# BTB_Connector_H.net
KiCad netlist of a schematic drawn in Altium Designer
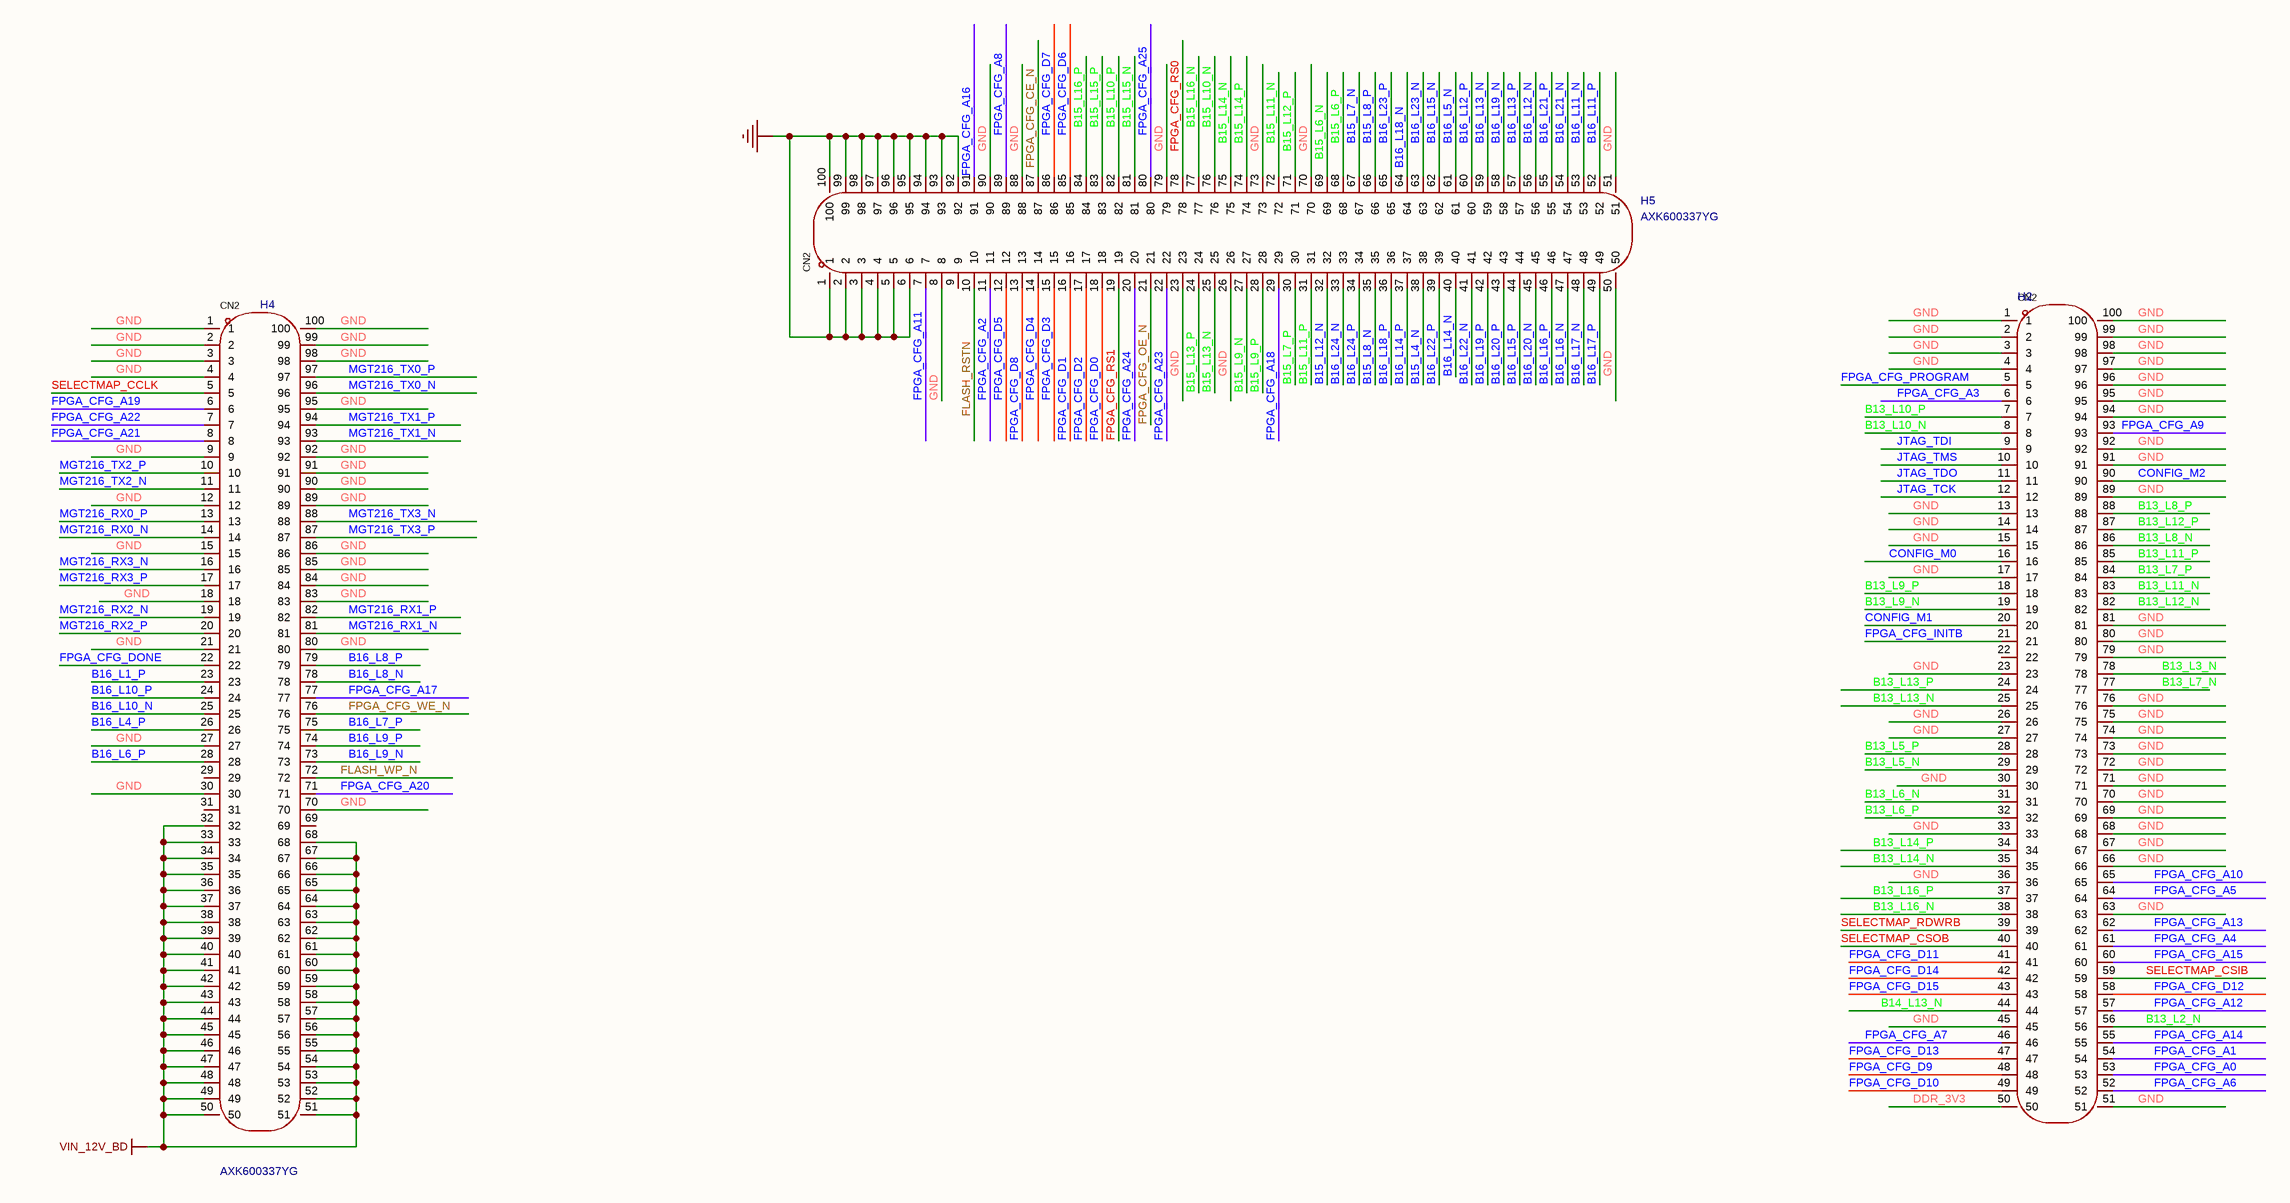
[diagram p0: BTB_Connector_H.schdoc]

(export (version "E")
  (design (tool "Eeschema 10.0.6"))
  (components
    (comp (ref "H2")
      (value "~")
      (footprint "AXK600337YG")
      (libsource (lib "altium-import") (part "root_0_AXK600337YG_"))
    )
    (comp (ref "H4")
      (value "~")
      (footprint "AXK600337YG")
      (fields (field (name "DEVICE") "AXK600337YG"))
      (libsource (lib "altium-import") (part "root_0_AXK600337YG_"))
    )
    (comp (ref "H5")
      (value "~")
      (footprint "AXK600337YG")
      (fields (field (name "DEVICE") "AXK600337YG"))
      (libsource (lib "altium-import") (part "root_1_AXK600337YG_"))
    )
  )
  (nets
    (net (code "1") (name "/B13_L2_N") (class "Default")
      (node (ref "H2") (pin "56") (pinfunction "56_56") (pintype "passive"))
    )
    (net (code "2") (name "/B13_L3_N") (class "Default")
      (node (ref "H2") (pin "78") (pinfunction "78_78") (pintype "passive"))
    )
    (net (code "3") (name "/B13_L5_N") (class "Default")
      (node (ref "H2") (pin "29") (pinfunction "29_29") (pintype "passive"))
    )
    (net (code "4") (name "/B13_L5_P") (class "Default")
      (node (ref "H2") (pin "28") (pinfunction "28_28") (pintype "passive"))
    )
    (net (code "5") (name "/B13_L6_N") (class "Default")
      (node (ref "H2") (pin "31") (pinfunction "31_31") (pintype "passive"))
    )
    (net (code "6") (name "/B13_L6_P") (class "Default")
      (node (ref "H2") (pin "32") (pinfunction "32_32") (pintype "passive"))
    )
    (net (code "7") (name "/B13_L7_N") (class "Default")
      (node (ref "H2") (pin "77") (pinfunction "77_77") (pintype "passive"))
    )
    (net (code "8") (name "/B13_L7_P") (class "Default")
      (node (ref "H2") (pin "84") (pinfunction "84_84") (pintype "passive"))
    )
    (net (code "9") (name "/B13_L8_N") (class "Default")
      (node (ref "H2") (pin "86") (pinfunction "86_86") (pintype "passive"))
    )
    (net (code "10") (name "/B13_L8_P") (class "Default")
      (node (ref "H2") (pin "88") (pinfunction "88_88") (pintype "passive"))
    )
    (net (code "11") (name "/B13_L9_N") (class "Default")
      (node (ref "H2") (pin "19") (pinfunction "19_19") (pintype "passive"))
    )
    (net (code "12") (name "/B13_L9_P") (class "Default")
      (node (ref "H2") (pin "18") (pinfunction "18_18") (pintype "passive"))
    )
    (net (code "13") (name "/B13_L10_N") (class "Default")
      (node (ref "H2") (pin "8") (pinfunction "8_8") (pintype "passive"))
    )
    (net (code "14") (name "/B13_L10_P") (class "Default")
      (node (ref "H2") (pin "7") (pinfunction "7_7") (pintype "passive"))
    )
    (net (code "15") (name "/B13_L11_N") (class "Default")
      (node (ref "H2") (pin "83") (pinfunction "83_83") (pintype "passive"))
    )
    (net (code "16") (name "/B13_L11_P") (class "Default")
      (node (ref "H2") (pin "85") (pinfunction "85_85") (pintype "passive"))
    )
    (net (code "17") (name "/B13_L12_N") (class "Default")
      (node (ref "H2") (pin "82") (pinfunction "82_82") (pintype "passive"))
    )
    (net (code "18") (name "/B13_L12_P") (class "Default")
      (node (ref "H2") (pin "87") (pinfunction "87_87") (pintype "passive"))
    )
    (net (code "19") (name "/B13_L13_N") (class "Default")
      (node (ref "H2") (pin "25") (pinfunction "25_25") (pintype "passive"))
    )
    (net (code "20") (name "/B13_L13_P") (class "Default")
      (node (ref "H2") (pin "24") (pinfunction "24_24") (pintype "passive"))
    )
    (net (code "21") (name "/B13_L14_N") (class "Default")
      (node (ref "H2") (pin "35") (pinfunction "35_35") (pintype "passive"))
    )
    (net (code "22") (name "/B13_L14_P") (class "Default")
      (node (ref "H2") (pin "34") (pinfunction "34_34") (pintype "passive"))
    )
    (net (code "23") (name "/B13_L16_N") (class "Default")
      (node (ref "H2") (pin "38") (pinfunction "38_38") (pintype "passive"))
    )
    (net (code "24") (name "/B13_L16_P") (class "Default")
      (node (ref "H2") (pin "37") (pinfunction "37_37") (pintype "passive"))
    )
    (net (code "25") (name "/B14_L13_N") (class "Default")
      (node (ref "H2") (pin "44") (pinfunction "44_44") (pintype "passive"))
    )
    (net (code "26") (name "/B15_L4_N") (class "Default")
      (node (ref "H5") (pin "38") (pinfunction "38_38") (pintype "passive"))
    )
    (net (code "27") (name "/B15_L6_N") (class "Default")
      (node (ref "H5") (pin "69") (pinfunction "69_69") (pintype "passive"))
    )
    (net (code "28") (name "/B15_L6_P") (class "Default")
      (node (ref "H5") (pin "68") (pinfunction "68_68") (pintype "passive"))
    )
    (net (code "29") (name "/B15_L7_N") (class "Default")
      (node (ref "H5") (pin "67") (pinfunction "67_67") (pintype "passive"))
    )
    (net (code "30") (name "/B15_L7_P") (class "Default")
      (node (ref "H5") (pin "30") (pinfunction "30_30") (pintype "passive"))
    )
    (net (code "31") (name "/B15_L8_N") (class "Default")
      (node (ref "H5") (pin "35") (pinfunction "35_35") (pintype "passive"))
    )
    (net (code "32") (name "/B15_L8_P") (class "Default")
      (node (ref "H5") (pin "66") (pinfunction "66_66") (pintype "passive"))
    )
    (net (code "33") (name "/B15_L9_N") (class "Default")
      (node (ref "H5") (pin "27") (pinfunction "27_27") (pintype "passive"))
    )
    (net (code "34") (name "/B15_L9_P") (class "Default")
      (node (ref "H5") (pin "28") (pinfunction "28_28") (pintype "passive"))
    )
    (net (code "35") (name "/B15_L10_N") (class "Default")
      (node (ref "H5") (pin "76") (pinfunction "76_76") (pintype "passive"))
    )
    (net (code "36") (name "/B15_L10_P") (class "Default")
      (node (ref "H5") (pin "82") (pinfunction "82_82") (pintype "passive"))
    )
    (net (code "37") (name "/B15_L11_N") (class "Default")
      (node (ref "H5") (pin "72") (pinfunction "72_72") (pintype "passive"))
    )
    (net (code "38") (name "/B15_L11_P") (class "Default")
      (node (ref "H5") (pin "31") (pinfunction "31_31") (pintype "passive"))
    )
    (net (code "39") (name "/B15_L12_N") (class "Default")
      (node (ref "H5") (pin "32") (pinfunction "32_32") (pintype "passive"))
    )
    (net (code "40") (name "/B15_L12_P") (class "Default")
      (node (ref "H5") (pin "71") (pinfunction "71_71") (pintype "passive"))
    )
    (net (code "41") (name "/B15_L13_N") (class "Default")
      (node (ref "H5") (pin "25") (pinfunction "25_25") (pintype "passive"))
    )
    (net (code "42") (name "/B15_L13_P") (class "Default")
      (node (ref "H5") (pin "24") (pinfunction "24_24") (pintype "passive"))
    )
    (net (code "43") (name "/B15_L14_N") (class "Default")
      (node (ref "H5") (pin "75") (pinfunction "75_75") (pintype "passive"))
    )
    (net (code "44") (name "/B15_L14_P") (class "Default")
      (node (ref "H5") (pin "74") (pinfunction "74_74") (pintype "passive"))
    )
    (net (code "45") (name "/B15_L15_N") (class "Default")
      (node (ref "H5") (pin "81") (pinfunction "81_81") (pintype "passive"))
    )
    (net (code "46") (name "/B15_L15_P") (class "Default")
      (node (ref "H5") (pin "83") (pinfunction "83_83") (pintype "passive"))
    )
    (net (code "47") (name "/B15_L16_N") (class "Default")
      (node (ref "H5") (pin "77") (pinfunction "77_77") (pintype "passive"))
    )
    (net (code "48") (name "/B15_L16_P") (class "Default")
      (node (ref "H5") (pin "84") (pinfunction "84_84") (pintype "passive"))
    )
    (net (code "49") (name "/B16_L1_P") (class "Default")
      (node (ref "H4") (pin "23") (pinfunction "23_23") (pintype "passive"))
    )
    (net (code "50") (name "/B16_L4_P") (class "Default")
      (node (ref "H4") (pin "26") (pinfunction "26_26") (pintype "passive"))
    )
    (net (code "51") (name "/B16_L5_N") (class "Default")
      (node (ref "H5") (pin "61") (pinfunction "61_61") (pintype "passive"))
    )
    (net (code "52") (name "/B16_L6_P") (class "Default")
      (node (ref "H4") (pin "28") (pinfunction "28_28") (pintype "passive"))
    )
    (net (code "53") (name "/B16_L7_P") (class "Default")
      (node (ref "H4") (pin "75") (pinfunction "75_75") (pintype "passive"))
    )
    (net (code "54") (name "/B16_L8_N") (class "Default")
      (node (ref "H4") (pin "78") (pinfunction "78_78") (pintype "passive"))
    )
    (net (code "55") (name "/B16_L8_P") (class "Default")
      (node (ref "H4") (pin "79") (pinfunction "79_79") (pintype "passive"))
    )
    (net (code "56") (name "/B16_L9_N") (class "Default")
      (node (ref "H4") (pin "73") (pinfunction "73_73") (pintype "passive"))
    )
    (net (code "57") (name "/B16_L9_P") (class "Default")
      (node (ref "H4") (pin "74") (pinfunction "74_74") (pintype "passive"))
    )
    (net (code "58") (name "/B16_L10_N") (class "Default")
      (node (ref "H4") (pin "25") (pinfunction "25_25") (pintype "passive"))
    )
    (net (code "59") (name "/B16_L10_P") (class "Default")
      (node (ref "H4") (pin "24") (pinfunction "24_24") (pintype "passive"))
    )
    (net (code "60") (name "/B16_L11_N") (class "Default")
      (node (ref "H5") (pin "53") (pinfunction "53_53") (pintype "passive"))
    )
    (net (code "61") (name "/B16_L11_P") (class "Default")
      (node (ref "H5") (pin "52") (pinfunction "52_52") (pintype "passive"))
    )
    (net (code "62") (name "/B16_L12_N") (class "Default")
      (node (ref "H5") (pin "56") (pinfunction "56_56") (pintype "passive"))
    )
    (net (code "63") (name "/B16_L12_P") (class "Default")
      (node (ref "H5") (pin "60") (pinfunction "60_60") (pintype "passive"))
    )
    (net (code "64") (name "/B16_L13_N") (class "Default")
      (node (ref "H5") (pin "59") (pinfunction "59_59") (pintype "passive"))
    )
    (net (code "65") (name "/B16_L13_P") (class "Default")
      (node (ref "H5") (pin "57") (pinfunction "57_57") (pintype "passive"))
    )
    (net (code "66") (name "/B16_L14_N") (class "Default")
      (node (ref "H5") (pin "40") (pinfunction "40_40") (pintype "passive"))
    )
    (net (code "67") (name "/B16_L14_P") (class "Default")
      (node (ref "H5") (pin "37") (pinfunction "37_37") (pintype "passive"))
    )
    (net (code "68") (name "/B16_L15_N") (class "Default")
      (node (ref "H5") (pin "62") (pinfunction "62_62") (pintype "passive"))
    )
    (net (code "69") (name "/B16_L15_P") (class "Default")
      (node (ref "H5") (pin "44") (pinfunction "44_44") (pintype "passive"))
    )
    (net (code "70") (name "/B16_L16_N") (class "Default")
      (node (ref "H5") (pin "47") (pinfunction "47_47") (pintype "passive"))
    )
    (net (code "71") (name "/B16_L16_P") (class "Default")
      (node (ref "H5") (pin "46") (pinfunction "46_46") (pintype "passive"))
    )
    (net (code "72") (name "/B16_L17_N") (class "Default")
      (node (ref "H5") (pin "48") (pinfunction "48_48") (pintype "passive"))
    )
    (net (code "73") (name "/B16_L17_P") (class "Default")
      (node (ref "H5") (pin "49") (pinfunction "49_49") (pintype "passive"))
    )
    (net (code "74") (name "/B16_L18_N") (class "Default")
      (node (ref "H5") (pin "64") (pinfunction "64_64") (pintype "passive"))
    )
    (net (code "75") (name "/B16_L18_P") (class "Default")
      (node (ref "H5") (pin "36") (pinfunction "36_36") (pintype "passive"))
    )
    (net (code "76") (name "/B16_L19_N") (class "Default")
      (node (ref "H5") (pin "58") (pinfunction "58_58") (pintype "passive"))
    )
    (net (code "77") (name "/B16_L19_P") (class "Default")
      (node (ref "H5") (pin "42") (pinfunction "42_42") (pintype "passive"))
    )
    (net (code "78") (name "/B16_L20_N") (class "Default")
      (node (ref "H5") (pin "45") (pinfunction "45_45") (pintype "passive"))
    )
    (net (code "79") (name "/B16_L20_P") (class "Default")
      (node (ref "H5") (pin "43") (pinfunction "43_43") (pintype "passive"))
    )
    (net (code "80") (name "/B16_L21_N") (class "Default")
      (node (ref "H5") (pin "54") (pinfunction "54_54") (pintype "passive"))
    )
    (net (code "81") (name "/B16_L21_P") (class "Default")
      (node (ref "H5") (pin "55") (pinfunction "55_55") (pintype "passive"))
    )
    (net (code "82") (name "/B16_L22_N") (class "Default")
      (node (ref "H5") (pin "41") (pinfunction "41_41") (pintype "passive"))
    )
    (net (code "83") (name "/B16_L22_P") (class "Default")
      (node (ref "H5") (pin "39") (pinfunction "39_39") (pintype "passive"))
    )
    (net (code "84") (name "/B16_L23_N") (class "Default")
      (node (ref "H5") (pin "63") (pinfunction "63_63") (pintype "passive"))
    )
    (net (code "85") (name "/B16_L23_P") (class "Default")
      (node (ref "H5") (pin "65") (pinfunction "65_65") (pintype "passive"))
    )
    (net (code "86") (name "/B16_L24_N") (class "Default")
      (node (ref "H5") (pin "33") (pinfunction "33_33") (pintype "passive"))
    )
    (net (code "87") (name "/B16_L24_P") (class "Default")
      (node (ref "H5") (pin "34") (pinfunction "34_34") (pintype "passive"))
    )
    (net (code "88") (name "/CONFIG_M0") (class "Default")
      (node (ref "H2") (pin "16") (pinfunction "16_16") (pintype "passive"))
    )
    (net (code "89") (name "/CONFIG_M1") (class "Default")
      (node (ref "H2") (pin "20") (pinfunction "20_20") (pintype "passive"))
    )
    (net (code "90") (name "/CONFIG_M2") (class "Default")
      (node (ref "H2") (pin "90") (pinfunction "90_90") (pintype "passive"))
    )
    (net (code "91") (name "/DDR_3V3") (class "Default")
      (node (ref "H2") (pin "50") (pinfunction "50_50") (pintype "passive"))
    )
    (net (code "92") (name "/FLASH_RSTN") (class "Default")
      (node (ref "H5") (pin "10") (pinfunction "10_10") (pintype "passive"))
    )
    (net (code "93") (name "/FLASH_WP_N") (class "Default")
      (node (ref "H4") (pin "72") (pinfunction "72_72") (pintype "passive"))
    )
    (net (code "94") (name "/FPGA_CFG_A0") (class "Default")
      (node (ref "H2") (pin "53") (pinfunction "53_53") (pintype "passive"))
    )
    (net (code "95") (name "/FPGA_CFG_A1") (class "Default")
      (node (ref "H2") (pin "54") (pinfunction "54_54") (pintype "passive"))
    )
    (net (code "96") (name "/FPGA_CFG_A2") (class "Default")
      (node (ref "H5") (pin "11") (pinfunction "11_11") (pintype "passive"))
    )
    (net (code "97") (name "/FPGA_CFG_A3") (class "Default")
      (node (ref "H2") (pin "6") (pinfunction "6_6") (pintype "passive"))
    )
    (net (code "98") (name "/FPGA_CFG_A4") (class "Default")
      (node (ref "H2") (pin "61") (pinfunction "61_61") (pintype "passive"))
    )
    (net (code "99") (name "/FPGA_CFG_A5") (class "Default")
      (node (ref "H2") (pin "64") (pinfunction "64_64") (pintype "passive"))
    )
    (net (code "100") (name "/FPGA_CFG_A6") (class "Default")
      (node (ref "H2") (pin "52") (pinfunction "52_52") (pintype "passive"))
    )
    (net (code "101") (name "/FPGA_CFG_A7") (class "Default")
      (node (ref "H2") (pin "46") (pinfunction "46_46") (pintype "passive"))
    )
    (net (code "102") (name "/FPGA_CFG_A8") (class "Default")
      (node (ref "H5") (pin "89") (pinfunction "89_89") (pintype "passive"))
    )
    (net (code "103") (name "/FPGA_CFG_A9") (class "Default")
      (node (ref "H2") (pin "93") (pinfunction "93_93") (pintype "passive"))
    )
    (net (code "104") (name "/FPGA_CFG_A10") (class "Default")
      (node (ref "H2") (pin "65") (pinfunction "65_65") (pintype "passive"))
    )
    (net (code "105") (name "/FPGA_CFG_A11") (class "Default")
      (node (ref "H5") (pin "7") (pinfunction "7_7") (pintype "passive"))
    )
    (net (code "106") (name "/FPGA_CFG_A12") (class "Default")
      (node (ref "H2") (pin "57") (pinfunction "57_57") (pintype "passive"))
    )
    (net (code "107") (name "/FPGA_CFG_A13") (class "Default")
      (node (ref "H2") (pin "62") (pinfunction "62_62") (pintype "passive"))
    )
    (net (code "108") (name "/FPGA_CFG_A14") (class "Default")
      (node (ref "H2") (pin "55") (pinfunction "55_55") (pintype "passive"))
    )
    (net (code "109") (name "/FPGA_CFG_A15") (class "Default")
      (node (ref "H2") (pin "60") (pinfunction "60_60") (pintype "passive"))
    )
    (net (code "110") (name "/FPGA_CFG_A16") (class "Default")
      (node (ref "H5") (pin "91") (pinfunction "91_91") (pintype "passive"))
    )
    (net (code "111") (name "/FPGA_CFG_A17") (class "Default")
      (node (ref "H4") (pin "77") (pinfunction "77_77") (pintype "passive"))
    )
    (net (code "112") (name "/FPGA_CFG_A18") (class "Default")
      (node (ref "H5") (pin "29") (pinfunction "29_29") (pintype "passive"))
    )
    (net (code "113") (name "/FPGA_CFG_A19") (class "Default")
      (node (ref "H4") (pin "6") (pinfunction "6_6") (pintype "passive"))
    )
    (net (code "114") (name "/FPGA_CFG_A20") (class "Default")
      (node (ref "H4") (pin "71") (pinfunction "71_71") (pintype "passive"))
    )
    (net (code "115") (name "/FPGA_CFG_A21") (class "Default")
      (node (ref "H4") (pin "8") (pinfunction "8_8") (pintype "passive"))
    )
    (net (code "116") (name "/FPGA_CFG_A22") (class "Default")
      (node (ref "H4") (pin "7") (pinfunction "7_7") (pintype "passive"))
    )
    (net (code "117") (name "/FPGA_CFG_A23") (class "Default")
      (node (ref "H5") (pin "22") (pinfunction "22_22") (pintype "passive"))
    )
    (net (code "118") (name "/FPGA_CFG_A24") (class "Default")
      (node (ref "H5") (pin "20") (pinfunction "20_20") (pintype "passive"))
    )
    (net (code "119") (name "/FPGA_CFG_A25") (class "Default")
      (node (ref "H5") (pin "80") (pinfunction "80_80") (pintype "passive"))
    )
    (net (code "120") (name "/FPGA_CFG_CE_N") (class "Default")
      (node (ref "H5") (pin "87") (pinfunction "87_87") (pintype "passive"))
    )
    (net (code "121") (name "/FPGA_CFG_D0") (class "Default")
      (node (ref "H5") (pin "18") (pinfunction "18_18") (pintype "passive"))
    )
    (net (code "122") (name "/FPGA_CFG_D1") (class "Default")
      (node (ref "H5") (pin "16") (pinfunction "16_16") (pintype "passive"))
    )
    (net (code "123") (name "/FPGA_CFG_D2") (class "Default")
      (node (ref "H5") (pin "17") (pinfunction "17_17") (pintype "passive"))
    )
    (net (code "124") (name "/FPGA_CFG_D3") (class "Default")
      (node (ref "H5") (pin "15") (pinfunction "15_15") (pintype "passive"))
    )
    (net (code "125") (name "/FPGA_CFG_D4") (class "Default")
      (node (ref "H5") (pin "14") (pinfunction "14_14") (pintype "passive"))
    )
    (net (code "126") (name "/FPGA_CFG_D5") (class "Default")
      (node (ref "H5") (pin "12") (pinfunction "12_12") (pintype "passive"))
    )
    (net (code "127") (name "/FPGA_CFG_D6") (class "Default")
      (node (ref "H5") (pin "85") (pinfunction "85_85") (pintype "passive"))
    )
    (net (code "128") (name "/FPGA_CFG_D7") (class "Default")
      (node (ref "H5") (pin "86") (pinfunction "86_86") (pintype "passive"))
    )
    (net (code "129") (name "/FPGA_CFG_D8") (class "Default")
      (node (ref "H5") (pin "13") (pinfunction "13_13") (pintype "passive"))
    )
    (net (code "130") (name "/FPGA_CFG_D9") (class "Default")
      (node (ref "H2") (pin "48") (pinfunction "48_48") (pintype "passive"))
    )
    (net (code "131") (name "/FPGA_CFG_D10") (class "Default")
      (node (ref "H2") (pin "49") (pinfunction "49_49") (pintype "passive"))
    )
    (net (code "132") (name "/FPGA_CFG_D11") (class "Default")
      (node (ref "H2") (pin "41") (pinfunction "41_41") (pintype "passive"))
    )
    (net (code "133") (name "/FPGA_CFG_D12") (class "Default")
      (node (ref "H2") (pin "58") (pinfunction "58_58") (pintype "passive"))
    )
    (net (code "134") (name "/FPGA_CFG_D13") (class "Default")
      (node (ref "H2") (pin "47") (pinfunction "47_47") (pintype "passive"))
    )
    (net (code "135") (name "/FPGA_CFG_D14") (class "Default")
      (node (ref "H2") (pin "42") (pinfunction "42_42") (pintype "passive"))
    )
    (net (code "136") (name "/FPGA_CFG_D15") (class "Default")
      (node (ref "H2") (pin "43") (pinfunction "43_43") (pintype "passive"))
    )
    (net (code "137") (name "/FPGA_CFG_DONE") (class "Default")
      (node (ref "H4") (pin "22") (pinfunction "22_22") (pintype "passive"))
    )
    (net (code "138") (name "/FPGA_CFG_INITB") (class "Default")
      (node (ref "H2") (pin "21") (pinfunction "21_21") (pintype "passive"))
    )
    (net (code "139") (name "/FPGA_CFG_OE_N") (class "Default")
      (node (ref "H5") (pin "21") (pinfunction "21_21") (pintype "passive"))
    )
    (net (code "140") (name "/FPGA_CFG_PROGRAM") (class "Default")
      (node (ref "H2") (pin "5") (pinfunction "5_5") (pintype "passive"))
    )
    (net (code "141") (name "/FPGA_CFG_RS0") (class "Default")
      (node (ref "H5") (pin "78") (pinfunction "78_78") (pintype "passive"))
    )
    (net (code "142") (name "/FPGA_CFG_RS1") (class "Default")
      (node (ref "H5") (pin "19") (pinfunction "19_19") (pintype "passive"))
    )
    (net (code "143") (name "/FPGA_CFG_WE_N") (class "Default")
      (node (ref "H4") (pin "76") (pinfunction "76_76") (pintype "passive"))
    )
    (net (code "144") (name "/JTAG_TCK") (class "Default")
      (node (ref "H2") (pin "12") (pinfunction "12_12") (pintype "passive"))
    )
    (net (code "145") (name "/JTAG_TDI") (class "Default")
      (node (ref "H2") (pin "9") (pinfunction "9_9") (pintype "passive"))
    )
    (net (code "146") (name "/JTAG_TDO") (class "Default")
      (node (ref "H2") (pin "11") (pinfunction "11_11") (pintype "passive"))
    )
    (net (code "147") (name "/JTAG_TMS") (class "Default")
      (node (ref "H2") (pin "10") (pinfunction "10_10") (pintype "passive"))
    )
    (net (code "148") (name "/MGT216_RX0_N") (class "Default")
      (node (ref "H4") (pin "14") (pinfunction "14_14") (pintype "passive"))
    )
    (net (code "149") (name "/MGT216_RX0_P") (class "Default")
      (node (ref "H4") (pin "13") (pinfunction "13_13") (pintype "passive"))
    )
    (net (code "150") (name "/MGT216_RX1_N") (class "Default")
      (node (ref "H4") (pin "81") (pinfunction "81_81") (pintype "passive"))
    )
    (net (code "151") (name "/MGT216_RX1_P") (class "Default")
      (node (ref "H4") (pin "82") (pinfunction "82_82") (pintype "passive"))
    )
    (net (code "152") (name "/MGT216_RX2_N") (class "Default")
      (node (ref "H4") (pin "19") (pinfunction "19_19") (pintype "passive"))
    )
    (net (code "153") (name "/MGT216_RX2_P") (class "Default")
      (node (ref "H4") (pin "20") (pinfunction "20_20") (pintype "passive"))
    )
    (net (code "154") (name "/MGT216_RX3_N") (class "Default")
      (node (ref "H4") (pin "16") (pinfunction "16_16") (pintype "passive"))
    )
    (net (code "155") (name "/MGT216_RX3_P") (class "Default")
      (node (ref "H4") (pin "17") (pinfunction "17_17") (pintype "passive"))
    )
    (net (code "156") (name "/MGT216_TX0_N") (class "Default")
      (node (ref "H4") (pin "96") (pinfunction "96_96") (pintype "passive"))
    )
    (net (code "157") (name "/MGT216_TX0_P") (class "Default")
      (node (ref "H4") (pin "97") (pinfunction "97_97") (pintype "passive"))
    )
    (net (code "158") (name "/MGT216_TX1_N") (class "Default")
      (node (ref "H4") (pin "93") (pinfunction "93_93") (pintype "passive"))
    )
    (net (code "159") (name "/MGT216_TX1_P") (class "Default")
      (node (ref "H4") (pin "94") (pinfunction "94_94") (pintype "passive"))
    )
    (net (code "160") (name "/MGT216_TX2_N") (class "Default")
      (node (ref "H4") (pin "11") (pinfunction "11_11") (pintype "passive"))
    )
    (net (code "161") (name "/MGT216_TX2_P") (class "Default")
      (node (ref "H4") (pin "10") (pinfunction "10_10") (pintype "passive"))
    )
    (net (code "162") (name "/MGT216_TX3_N") (class "Default")
      (node (ref "H4") (pin "88") (pinfunction "88_88") (pintype "passive"))
    )
    (net (code "163") (name "/MGT216_TX3_P") (class "Default")
      (node (ref "H4") (pin "87") (pinfunction "87_87") (pintype "passive"))
    )
    (net (code "164") (name "/SELECTMAP_CCLK") (class "Default")
      (node (ref "H4") (pin "5") (pinfunction "5_5") (pintype "passive"))
    )
    (net (code "165") (name "/SELECTMAP_CSIB") (class "Default")
      (node (ref "H2") (pin "59") (pinfunction "59_59") (pintype "passive"))
    )
    (net (code "166") (name "/SELECTMAP_CSOB") (class "Default")
      (node (ref "H2") (pin "40") (pinfunction "40_40") (pintype "passive"))
    )
    (net (code "167") (name "/SELECTMAP_RDWRB") (class "Default")
      (node (ref "H2") (pin "39") (pinfunction "39_39") (pintype "passive"))
    )
    (net (code "168") (name "GND") (class "Default")
      (node (ref "H2") (pin "1") (pinfunction "1_1") (pintype "passive"))
      (node (ref "H2") (pin "100") (pinfunction "100_100") (pintype "passive"))
      (node (ref "H2") (pin "13") (pinfunction "13_13") (pintype "passive"))
      (node (ref "H2") (pin "14") (pinfunction "14_14") (pintype "passive"))
      (node (ref "H2") (pin "15") (pinfunction "15_15") (pintype "passive"))
      (node (ref "H2") (pin "17") (pinfunction "17_17") (pintype "passive"))
      (node (ref "H2") (pin "2") (pinfunction "2_2") (pintype "passive"))
      (node (ref "H2") (pin "23") (pinfunction "23_23") (pintype "passive"))
      (node (ref "H2") (pin "26") (pinfunction "26_26") (pintype "passive"))
      (node (ref "H2") (pin "27") (pinfunction "27_27") (pintype "passive"))
      (node (ref "H2") (pin "3") (pinfunction "3_3") (pintype "passive"))
      (node (ref "H2") (pin "30") (pinfunction "30_30") (pintype "passive"))
      (node (ref "H2") (pin "33") (pinfunction "33_33") (pintype "passive"))
      (node (ref "H2") (pin "36") (pinfunction "36_36") (pintype "passive"))
      (node (ref "H2") (pin "4") (pinfunction "4_4") (pintype "passive"))
      (node (ref "H2") (pin "45") (pinfunction "45_45") (pintype "passive"))
      (node (ref "H2") (pin "51") (pinfunction "51_51") (pintype "passive"))
      (node (ref "H2") (pin "63") (pinfunction "63_63") (pintype "passive"))
      (node (ref "H2") (pin "66") (pinfunction "66_66") (pintype "passive"))
      (node (ref "H2") (pin "67") (pinfunction "67_67") (pintype "passive"))
      (node (ref "H2") (pin "68") (pinfunction "68_68") (pintype "passive"))
      (node (ref "H2") (pin "69") (pinfunction "69_69") (pintype "passive"))
      (node (ref "H2") (pin "70") (pinfunction "70_70") (pintype "passive"))
      (node (ref "H2") (pin "71") (pinfunction "71_71") (pintype "passive"))
      (node (ref "H2") (pin "72") (pinfunction "72_72") (pintype "passive"))
      (node (ref "H2") (pin "73") (pinfunction "73_73") (pintype "passive"))
      (node (ref "H2") (pin "74") (pinfunction "74_74") (pintype "passive"))
      (node (ref "H2") (pin "75") (pinfunction "75_75") (pintype "passive"))
      (node (ref "H2") (pin "76") (pinfunction "76_76") (pintype "passive"))
      (node (ref "H2") (pin "79") (pinfunction "79_79") (pintype "passive"))
      (node (ref "H2") (pin "80") (pinfunction "80_80") (pintype "passive"))
      (node (ref "H2") (pin "81") (pinfunction "81_81") (pintype "passive"))
      (node (ref "H2") (pin "89") (pinfunction "89_89") (pintype "passive"))
      (node (ref "H2") (pin "91") (pinfunction "91_91") (pintype "passive"))
      (node (ref "H2") (pin "92") (pinfunction "92_92") (pintype "passive"))
      (node (ref "H2") (pin "94") (pinfunction "94_94") (pintype "passive"))
      (node (ref "H2") (pin "95") (pinfunction "95_95") (pintype "passive"))
      (node (ref "H2") (pin "96") (pinfunction "96_96") (pintype "passive"))
      (node (ref "H2") (pin "97") (pinfunction "97_97") (pintype "passive"))
      (node (ref "H2") (pin "98") (pinfunction "98_98") (pintype "passive"))
      (node (ref "H2") (pin "99") (pinfunction "99_99") (pintype "passive"))
      (node (ref "H4") (pin "1") (pinfunction "1_1") (pintype "passive"))
      (node (ref "H4") (pin "100") (pinfunction "100_100") (pintype "passive"))
      (node (ref "H4") (pin "12") (pinfunction "12_12") (pintype "passive"))
      (node (ref "H4") (pin "15") (pinfunction "15_15") (pintype "passive"))
      (node (ref "H4") (pin "18") (pinfunction "18_18") (pintype "passive"))
      (node (ref "H4") (pin "2") (pinfunction "2_2") (pintype "passive"))
      (node (ref "H4") (pin "21") (pinfunction "21_21") (pintype "passive"))
      (node (ref "H4") (pin "27") (pinfunction "27_27") (pintype "passive"))
      (node (ref "H4") (pin "3") (pinfunction "3_3") (pintype "passive"))
      (node (ref "H4") (pin "30") (pinfunction "30_30") (pintype "passive"))
      (node (ref "H4") (pin "4") (pinfunction "4_4") (pintype "passive"))
      (node (ref "H4") (pin "70") (pinfunction "70_70") (pintype "passive"))
      (node (ref "H4") (pin "80") (pinfunction "80_80") (pintype "passive"))
      (node (ref "H4") (pin "83") (pinfunction "83_83") (pintype "passive"))
      (node (ref "H4") (pin "84") (pinfunction "84_84") (pintype "passive"))
      (node (ref "H4") (pin "85") (pinfunction "85_85") (pintype "passive"))
      (node (ref "H4") (pin "86") (pinfunction "86_86") (pintype "passive"))
      (node (ref "H4") (pin "89") (pinfunction "89_89") (pintype "passive"))
      (node (ref "H4") (pin "9") (pinfunction "9_9") (pintype "passive"))
      (node (ref "H4") (pin "90") (pinfunction "90_90") (pintype "passive"))
      (node (ref "H4") (pin "91") (pinfunction "91_91") (pintype "passive"))
      (node (ref "H4") (pin "92") (pinfunction "92_92") (pintype "passive"))
      (node (ref "H4") (pin "95") (pinfunction "95_95") (pintype "passive"))
      (node (ref "H4") (pin "98") (pinfunction "98_98") (pintype "passive"))
      (node (ref "H4") (pin "99") (pinfunction "99_99") (pintype "passive"))
      (node (ref "H5") (pin "1") (pinfunction "1_1") (pintype "passive"))
      (node (ref "H5") (pin "100") (pinfunction "100_100") (pintype "passive"))
      (node (ref "H5") (pin "2") (pinfunction "2_2") (pintype "passive"))
      (node (ref "H5") (pin "23") (pinfunction "23_23") (pintype "passive"))
      (node (ref "H5") (pin "26") (pinfunction "26_26") (pintype "passive"))
      (node (ref "H5") (pin "3") (pinfunction "3_3") (pintype "passive"))
      (node (ref "H5") (pin "4") (pinfunction "4_4") (pintype "passive"))
      (node (ref "H5") (pin "5") (pinfunction "5_5") (pintype "passive"))
      (node (ref "H5") (pin "50") (pinfunction "50_50") (pintype "passive"))
      (node (ref "H5") (pin "51") (pinfunction "51_51") (pintype "passive"))
      (node (ref "H5") (pin "6") (pinfunction "6_6") (pintype "passive"))
      (node (ref "H5") (pin "70") (pinfunction "70_70") (pintype "passive"))
      (node (ref "H5") (pin "73") (pinfunction "73_73") (pintype "passive"))
      (node (ref "H5") (pin "79") (pinfunction "79_79") (pintype "passive"))
      (node (ref "H5") (pin "8") (pinfunction "8_8") (pintype "passive"))
      (node (ref "H5") (pin "88") (pinfunction "88_88") (pintype "passive"))
      (node (ref "H5") (pin "90") (pinfunction "90_90") (pintype "passive"))
      (node (ref "H5") (pin "92") (pinfunction "92_92") (pintype "passive"))
      (node (ref "H5") (pin "93") (pinfunction "93_93") (pintype "passive"))
      (node (ref "H5") (pin "94") (pinfunction "94_94") (pintype "passive"))
      (node (ref "H5") (pin "95") (pinfunction "95_95") (pintype "passive"))
      (node (ref "H5") (pin "96") (pinfunction "96_96") (pintype "passive"))
      (node (ref "H5") (pin "97") (pinfunction "97_97") (pintype "passive"))
      (node (ref "H5") (pin "98") (pinfunction "98_98") (pintype "passive"))
      (node (ref "H5") (pin "99") (pinfunction "99_99") (pintype "passive"))
    )
    (net (code "169") (name "VIN_12V_BD") (class "Default")
      (node (ref "H4") (pin "32") (pinfunction "32_32") (pintype "passive"))
      (node (ref "H4") (pin "33") (pinfunction "33_33") (pintype "passive"))
      (node (ref "H4") (pin "34") (pinfunction "34_34") (pintype "passive"))
      (node (ref "H4") (pin "35") (pinfunction "35_35") (pintype "passive"))
      (node (ref "H4") (pin "36") (pinfunction "36_36") (pintype "passive"))
      (node (ref "H4") (pin "37") (pinfunction "37_37") (pintype "passive"))
      (node (ref "H4") (pin "38") (pinfunction "38_38") (pintype "passive"))
      (node (ref "H4") (pin "39") (pinfunction "39_39") (pintype "passive"))
      (node (ref "H4") (pin "40") (pinfunction "40_40") (pintype "passive"))
      (node (ref "H4") (pin "41") (pinfunction "41_41") (pintype "passive"))
      (node (ref "H4") (pin "42") (pinfunction "42_42") (pintype "passive"))
      (node (ref "H4") (pin "43") (pinfunction "43_43") (pintype "passive"))
      (node (ref "H4") (pin "44") (pinfunction "44_44") (pintype "passive"))
      (node (ref "H4") (pin "45") (pinfunction "45_45") (pintype "passive"))
      (node (ref "H4") (pin "46") (pinfunction "46_46") (pintype "passive"))
      (node (ref "H4") (pin "47") (pinfunction "47_47") (pintype "passive"))
      (node (ref "H4") (pin "48") (pinfunction "48_48") (pintype "passive"))
      (node (ref "H4") (pin "49") (pinfunction "49_49") (pintype "passive"))
      (node (ref "H4") (pin "50") (pinfunction "50_50") (pintype "passive"))
      (node (ref "H4") (pin "51") (pinfunction "51_51") (pintype "passive"))
      (node (ref "H4") (pin "52") (pinfunction "52_52") (pintype "passive"))
      (node (ref "H4") (pin "53") (pinfunction "53_53") (pintype "passive"))
      (node (ref "H4") (pin "54") (pinfunction "54_54") (pintype "passive"))
      (node (ref "H4") (pin "55") (pinfunction "55_55") (pintype "passive"))
      (node (ref "H4") (pin "56") (pinfunction "56_56") (pintype "passive"))
      (node (ref "H4") (pin "57") (pinfunction "57_57") (pintype "passive"))
      (node (ref "H4") (pin "58") (pinfunction "58_58") (pintype "passive"))
      (node (ref "H4") (pin "59") (pinfunction "59_59") (pintype "passive"))
      (node (ref "H4") (pin "60") (pinfunction "60_60") (pintype "passive"))
      (node (ref "H4") (pin "61") (pinfunction "61_61") (pintype "passive"))
      (node (ref "H4") (pin "62") (pinfunction "62_62") (pintype "passive"))
      (node (ref "H4") (pin "63") (pinfunction "63_63") (pintype "passive"))
      (node (ref "H4") (pin "64") (pinfunction "64_64") (pintype "passive"))
      (node (ref "H4") (pin "65") (pinfunction "65_65") (pintype "passive"))
      (node (ref "H4") (pin "66") (pinfunction "66_66") (pintype "passive"))
      (node (ref "H4") (pin "67") (pinfunction "67_67") (pintype "passive"))
      (node (ref "H4") (pin "68") (pinfunction "68_68") (pintype "passive"))
    )
    (net (code "170") (name "unconnected-(H2-Pad22)") (class "Default")
      (node (ref "H2") (pin "22") (pinfunction "22_22") (pintype "passive"))
    )
    (net (code "171") (name "unconnected-(H4-Pad29)") (class "Default")
      (node (ref "H4") (pin "29") (pinfunction "29_29") (pintype "passive"))
    )
    (net (code "172") (name "unconnected-(H4-Pad31)") (class "Default")
      (node (ref "H4") (pin "31") (pinfunction "31_31") (pintype "passive"))
    )
    (net (code "173") (name "unconnected-(H4-Pad69)") (class "Default")
      (node (ref "H4") (pin "69") (pinfunction "69_69") (pintype "passive"))
    )
    (net (code "174") (name "unconnected-(H5-Pad9)") (class "Default")
      (node (ref "H5") (pin "9") (pinfunction "9_9") (pintype "passive"))
    )
  )
)
